# PA.net
KiCad netlist of a schematic drawn in EAGLE
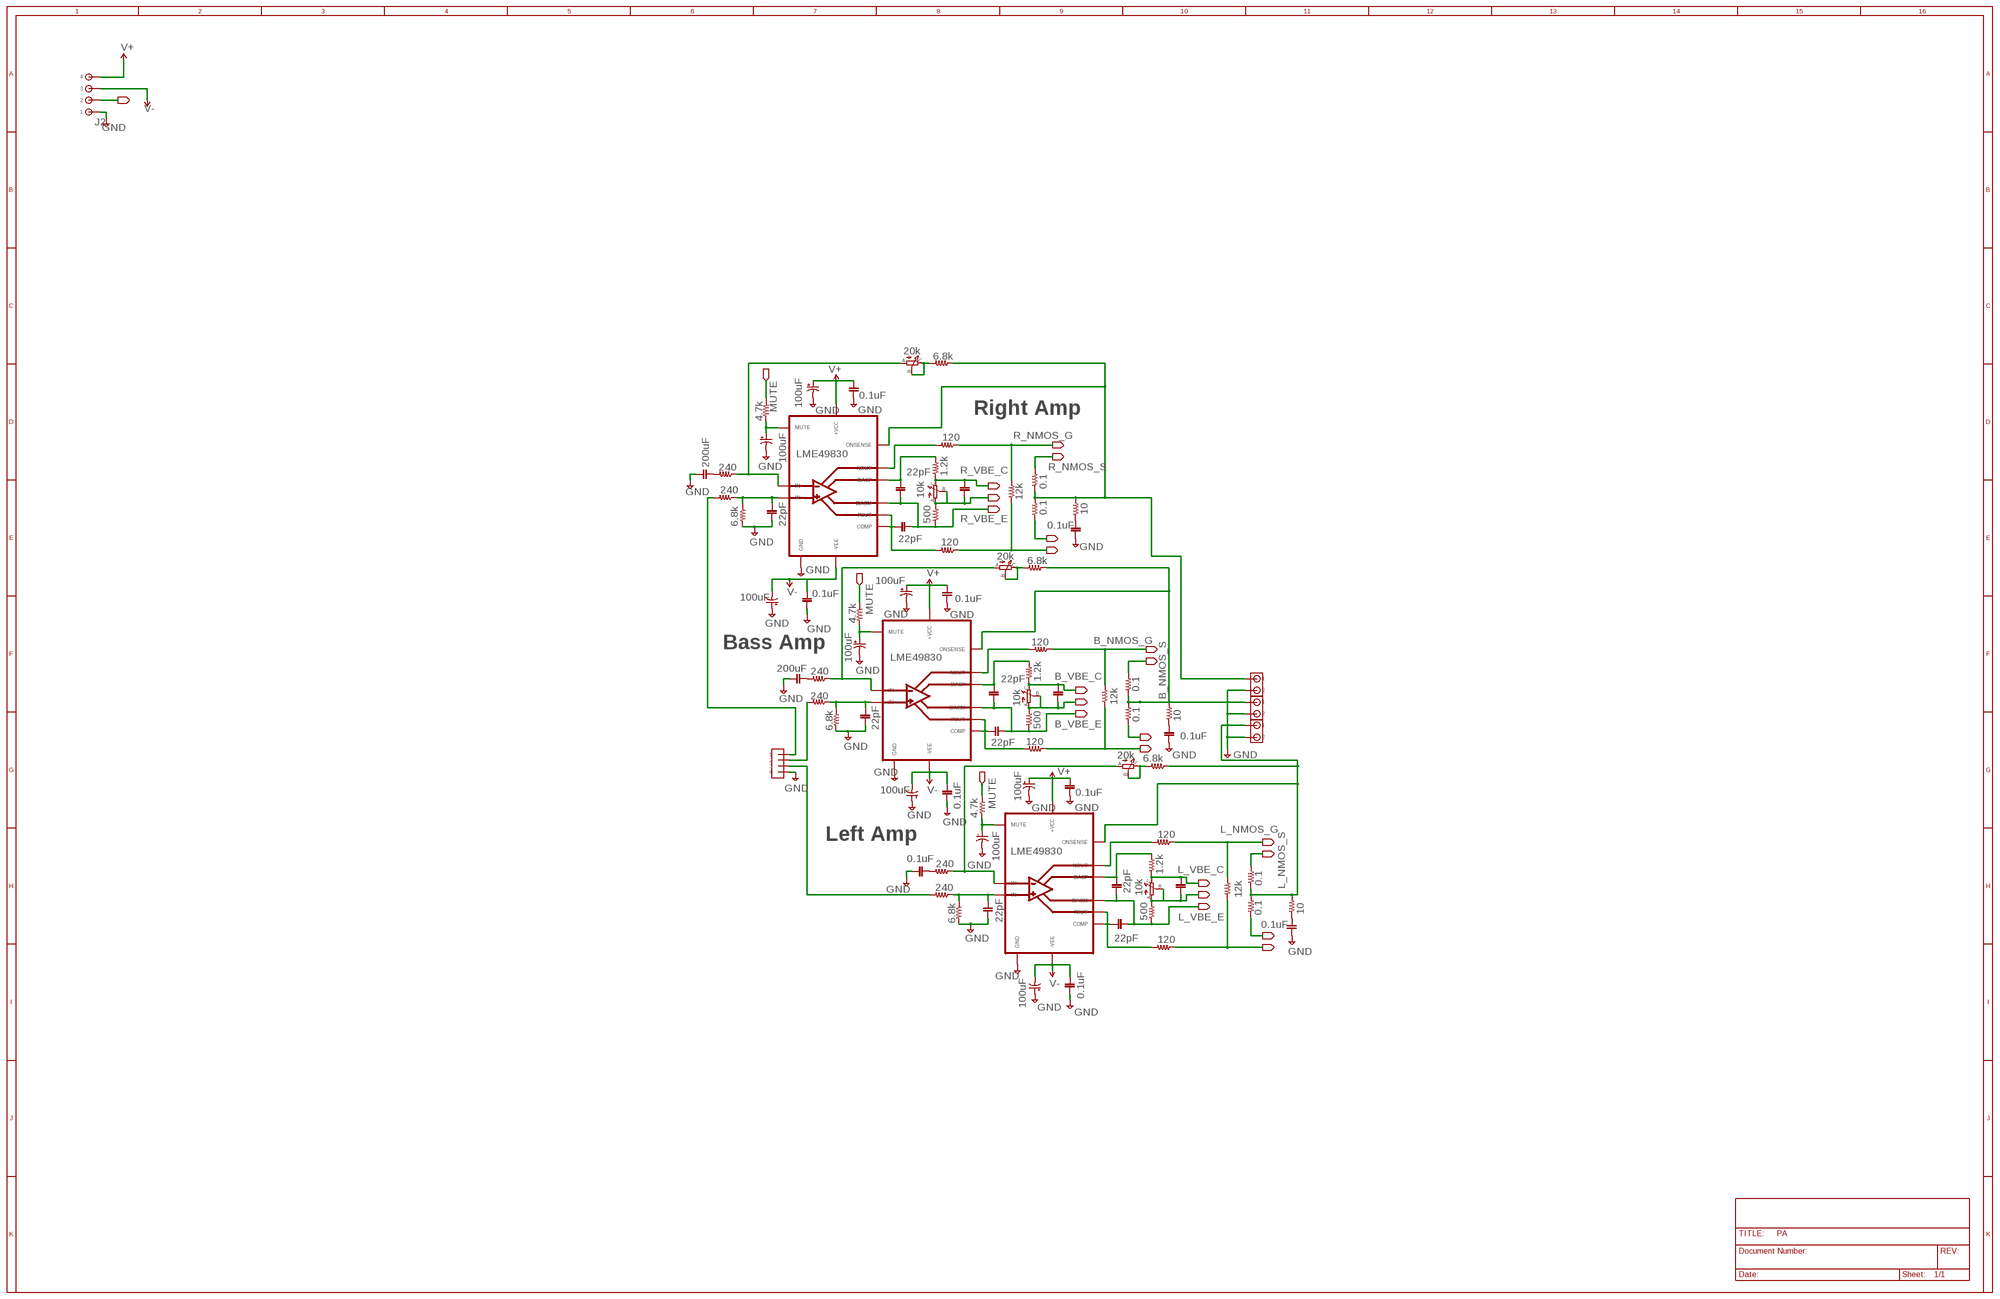
[diagram p0: schematic, sheet 1]

(export (version "E")
  (design (tool "Eeschema 10.0.6"))
  (components
    (comp (ref "C1")
      (value "22pF")
      (footprint "eagle-import:C050-024X044")
      (libsource (lib "eagle-import") (part "C-EU050-024X044"))
    )
    (comp (ref "C2")
      (value "100uF")
      (footprint "eagle-import:E2,5-6")
      (libsource (lib "eagle-import") (part "CPOL-USE2.5-6"))
    )
    (comp (ref "C3")
      (value "0.1uF")
      (footprint "eagle-import:C050-024X044")
      (libsource (lib "eagle-import") (part "C-EU050-024X044"))
    )
    (comp (ref "C4")
      (value "100uF")
      (footprint "eagle-import:E2,5-6")
      (libsource (lib "eagle-import") (part "CPOL-USE2.5-6"))
    )
    (comp (ref "C5")
      (value "0.1uF")
      (footprint "eagle-import:C050-024X044")
      (libsource (lib "eagle-import") (part "C-EU050-024X044"))
    )
    (comp (ref "C6")
      (value "100uF")
      (footprint "eagle-import:E2,5-6")
      (libsource (lib "eagle-import") (part "CPOL-USE2.5-6"))
    )
    (comp (ref "C7")
      (value "200uF")
      (footprint "eagle-import:C050-024X044")
      (libsource (lib "eagle-import") (part "C-EU050-024X044"))
    )
    (comp (ref "C8")
      (value "22pF")
      (footprint "eagle-import:C050-024X044")
      (libsource (lib "eagle-import") (part "C-EU050-024X044"))
    )
    (comp (ref "C9")
      (value "22pF")
      (footprint "eagle-import:C050-024X044")
      (libsource (lib "eagle-import") (part "C-EU050-024X044"))
    )
    (comp (ref "C10")
      (value "22pF")
      (footprint "eagle-import:C050-024X044")
      (libsource (lib "eagle-import") (part "C-EU050-024X044"))
    )
    (comp (ref "C15")
      (value "0.1uF")
      (footprint "eagle-import:C050-024X044")
      (libsource (lib "eagle-import") (part "C-EU050-024X044"))
    )
    (comp (ref "C16")
      (value "100uF")
      (footprint "eagle-import:E2,5-6")
      (libsource (lib "eagle-import") (part "CPOL-USE2.5-6"))
    )
    (comp (ref "C17")
      (value "100uF")
      (footprint "eagle-import:E2,5-6")
      (libsource (lib "eagle-import") (part "CPOL-USE2.5-6"))
    )
    (comp (ref "C18")
      (value "0.1uF")
      (footprint "eagle-import:C050-024X044")
      (libsource (lib "eagle-import") (part "C-EU050-024X044"))
    )
    (comp (ref "C19")
      (value "0.1uF")
      (footprint "eagle-import:C050-024X044")
      (libsource (lib "eagle-import") (part "C-EU050-024X044"))
    )
    (comp (ref "C20")
      (value "22pF")
      (footprint "eagle-import:C050-024X044")
      (libsource (lib "eagle-import") (part "C-EU050-024X044"))
    )
    (comp (ref "C21")
      (value "22pF")
      (footprint "eagle-import:C050-024X044")
      (libsource (lib "eagle-import") (part "C-EU050-024X044"))
    )
    (comp (ref "C22")
      (value "22pF")
      (footprint "eagle-import:C050-024X044")
      (libsource (lib "eagle-import") (part "C-EU050-024X044"))
    )
    (comp (ref "C27")
      (value "0.1uF")
      (footprint "eagle-import:C050-024X044")
      (libsource (lib "eagle-import") (part "C-EU050-024X044"))
    )
    (comp (ref "C28")
      (value "100uF")
      (footprint "eagle-import:E2,5-6")
      (libsource (lib "eagle-import") (part "CPOL-USE2.5-6"))
    )
    (comp (ref "C29")
      (value "22pF")
      (footprint "eagle-import:C050-024X044")
      (libsource (lib "eagle-import") (part "C-EU050-024X044"))
    )
    (comp (ref "C30")
      (value "200uF")
      (footprint "eagle-import:C050-024X044")
      (libsource (lib "eagle-import") (part "C-EU050-024X044"))
    )
    (comp (ref "C31")
      (value "100uF")
      (footprint "eagle-import:E2,5-6")
      (libsource (lib "eagle-import") (part "CPOL-USE2.5-6"))
    )
    (comp (ref "C32")
      (value "100uF")
      (footprint "eagle-import:E2,5-6")
      (libsource (lib "eagle-import") (part "CPOL-USE2.5-6"))
    )
    (comp (ref "C33")
      (value "0.1uF")
      (footprint "eagle-import:C050-024X044")
      (libsource (lib "eagle-import") (part "C-EU050-024X044"))
    )
    (comp (ref "C34")
      (value "0.1uF")
      (footprint "eagle-import:C050-024X044")
      (libsource (lib "eagle-import") (part "C-EU050-024X044"))
    )
    (comp (ref "C35")
      (value "22pF")
      (footprint "eagle-import:C050-024X044")
      (libsource (lib "eagle-import") (part "C-EU050-024X044"))
    )
    (comp (ref "C36")
      (value "22pF")
      (footprint "eagle-import:C050-024X044")
      (libsource (lib "eagle-import") (part "C-EU050-024X044"))
    )
    (comp (ref "C37")
      (value "22pF")
      (footprint "eagle-import:C050-024X044")
      (libsource (lib "eagle-import") (part "C-EU050-024X044"))
    )
    (comp (ref "C42")
      (value "0.1uF")
      (footprint "eagle-import:C050-024X044")
      (libsource (lib "eagle-import") (part "C-EU050-024X044"))
    )
    (comp (ref "C43")
      (value "100uF")
      (footprint "eagle-import:E2,5-6")
      (libsource (lib "eagle-import") (part "CPOL-USE2.5-6"))
    )
    (comp (ref "C44")
      (value "22pF")
      (footprint "eagle-import:C050-024X044")
      (libsource (lib "eagle-import") (part "C-EU050-024X044"))
    )
    (comp (ref "C45")
      (value "0.1uF")
      (footprint "eagle-import:C050-024X044")
      (libsource (lib "eagle-import") (part "C-EU050-024X044"))
    )
    (comp (ref "J1")
      (value "4_PIN_AMPCONN")
      (footprint "eagle-import:4_PIN_AMPCON")
      (libsource (lib "eagle-import") (part "4_PIN_AMPCONN"))
    )
    (comp (ref "J2")
      (value "1984633")
      (footprint "eagle-import:1984633")
      (libsource (lib "eagle-import") (part "1984633"))
    )
    (comp (ref "J3")
      (value "2TERMINAL_SPEAKER")
      (footprint "eagle-import:2TERMINAL_SPEAKER")
      (libsource (lib "eagle-import") (part "2TERMINAL_SPEAKER"))
    )
    (comp (ref "J4")
      (value "2TERMINAL_SPEAKER")
      (footprint "eagle-import:2TERMINAL_SPEAKER")
      (libsource (lib "eagle-import") (part "2TERMINAL_SPEAKER"))
    )
    (comp (ref "J5")
      (value "2TERMINAL_SPEAKER")
      (footprint "eagle-import:2TERMINAL_SPEAKER")
      (libsource (lib "eagle-import") (part "2TERMINAL_SPEAKER"))
    )
    (comp (ref "PR1")
      (value "0.1")
      (footprint "eagle-import:0617V")
      (libsource (lib "eagle-import") (part "R-US_0617/5V"))
    )
    (comp (ref "PR2")
      (value "0.1")
      (footprint "eagle-import:0617V")
      (libsource (lib "eagle-import") (part "R-US_0617/5V"))
    )
    (comp (ref "PR3")
      (value "0.1")
      (footprint "eagle-import:0617V")
      (libsource (lib "eagle-import") (part "R-US_0617/5V"))
    )
    (comp (ref "PR4")
      (value "0.1")
      (footprint "eagle-import:0617V")
      (libsource (lib "eagle-import") (part "R-US_0617/5V"))
    )
    (comp (ref "PR5")
      (value "0.1")
      (footprint "eagle-import:0617V")
      (libsource (lib "eagle-import") (part "R-US_0617/5V"))
    )
    (comp (ref "PR6")
      (value "0.1")
      (footprint "eagle-import:0617V")
      (libsource (lib "eagle-import") (part "R-US_0617/5V"))
    )
    (comp (ref "R1")
      (value "240")
      (footprint "eagle-import:0204V")
      (libsource (lib "eagle-import") (part "R-US_0204/2V"))
    )
    (comp (ref "R2")
      (value "6.8k")
      (footprint "eagle-import:0204V")
      (libsource (lib "eagle-import") (part "R-US_0204/2V"))
    )
    (comp (ref "R3")
      (value "1.2k")
      (footprint "eagle-import:0204V")
      (libsource (lib "eagle-import") (part "R-US_0204/2V"))
    )
    (comp (ref "R4")
      (value "500")
      (footprint "eagle-import:0204V")
      (libsource (lib "eagle-import") (part "R-US_0204/2V"))
    )
    (comp (ref "R5")
      (value "12k")
      (footprint "eagle-import:0204V")
      (libsource (lib "eagle-import") (part "R-US_0204/2V"))
    )
    (comp (ref "R6")
      (value "120")
      (footprint "eagle-import:0204V")
      (libsource (lib "eagle-import") (part "R-US_0204/2V"))
    )
    (comp (ref "R7")
      (value "120")
      (footprint "eagle-import:0204V")
      (libsource (lib "eagle-import") (part "R-US_0204/2V"))
    )
    (comp (ref "R8")
      (value "10")
      (footprint "eagle-import:0309V")
      (libsource (lib "eagle-import") (part "R-US_0309/V"))
    )
    (comp (ref "R9")
      (value "4.7k")
      (footprint "eagle-import:0204V")
      (libsource (lib "eagle-import") (part "R-US_0204/2V"))
    )
    (comp (ref "R10")
      (value "6.8k")
      (footprint "eagle-import:0204V")
      (libsource (lib "eagle-import") (part "R-US_0204/2V"))
    )
    (comp (ref "R11")
      (value "240")
      (footprint "eagle-import:0204V")
      (libsource (lib "eagle-import") (part "R-US_0204/2V"))
    )
    (comp (ref "R12")
      (value "240")
      (footprint "eagle-import:0204V")
      (libsource (lib "eagle-import") (part "R-US_0204/2V"))
    )
    (comp (ref "R13")
      (value "6.8k")
      (footprint "eagle-import:0204V")
      (libsource (lib "eagle-import") (part "R-US_0204/2V"))
    )
    (comp (ref "R14")
      (value "1.2k")
      (footprint "eagle-import:0204V")
      (libsource (lib "eagle-import") (part "R-US_0204/2V"))
    )
    (comp (ref "R15")
      (value "500")
      (footprint "eagle-import:0204V")
      (libsource (lib "eagle-import") (part "R-US_0204/2V"))
    )
    (comp (ref "R16")
      (value "12k")
      (footprint "eagle-import:0204V")
      (libsource (lib "eagle-import") (part "R-US_0204/2V"))
    )
    (comp (ref "R17")
      (value "120")
      (footprint "eagle-import:0204V")
      (libsource (lib "eagle-import") (part "R-US_0204/2V"))
    )
    (comp (ref "R18")
      (value "120")
      (footprint "eagle-import:0204V")
      (libsource (lib "eagle-import") (part "R-US_0204/2V"))
    )
    (comp (ref "R19")
      (value "10")
      (footprint "eagle-import:0309V")
      (libsource (lib "eagle-import") (part "R-US_0309/V"))
    )
    (comp (ref "R20")
      (value "4.7k")
      (footprint "eagle-import:0204V")
      (libsource (lib "eagle-import") (part "R-US_0204/2V"))
    )
    (comp (ref "R21")
      (value "6.8k")
      (footprint "eagle-import:0204V")
      (libsource (lib "eagle-import") (part "R-US_0204/2V"))
    )
    (comp (ref "R22")
      (value "240")
      (footprint "eagle-import:0204V")
      (libsource (lib "eagle-import") (part "R-US_0204/2V"))
    )
    (comp (ref "R23")
      (value "240")
      (footprint "eagle-import:0204V")
      (libsource (lib "eagle-import") (part "R-US_0204/2V"))
    )
    (comp (ref "R24")
      (value "6.8k")
      (footprint "eagle-import:0204V")
      (libsource (lib "eagle-import") (part "R-US_0204/2V"))
    )
    (comp (ref "R44")
      (value "1.2k")
      (footprint "eagle-import:0204V")
      (libsource (lib "eagle-import") (part "R-US_0204/2V"))
    )
    (comp (ref "R45")
      (value "500")
      (footprint "eagle-import:0204V")
      (libsource (lib "eagle-import") (part "R-US_0204/2V"))
    )
    (comp (ref "R46")
      (value "12k")
      (footprint "eagle-import:0204V")
      (libsource (lib "eagle-import") (part "R-US_0204/2V"))
    )
    (comp (ref "R47")
      (value "120")
      (footprint "eagle-import:0204V")
      (libsource (lib "eagle-import") (part "R-US_0204/2V"))
    )
    (comp (ref "R48")
      (value "120")
      (footprint "eagle-import:0204V")
      (libsource (lib "eagle-import") (part "R-US_0204/2V"))
    )
    (comp (ref "R51")
      (value "10")
      (footprint "eagle-import:0309V")
      (libsource (lib "eagle-import") (part "R-US_0309/V"))
    )
    (comp (ref "R52")
      (value "4.7k")
      (footprint "eagle-import:0204V")
      (libsource (lib "eagle-import") (part "R-US_0204/2V"))
    )
    (comp (ref "R55")
      (value "240")
      (footprint "eagle-import:0204V")
      (libsource (lib "eagle-import") (part "R-US_0204/2V"))
    )
    (comp (ref "R56")
      (value "6.8k")
      (footprint "eagle-import:0204V")
      (libsource (lib "eagle-import") (part "R-US_0204/2V"))
    )
    (comp (ref "U1")
      (value "LME49830")
      (footprint "eagle-import:NDN0015A")
      (libsource (lib "eagle-import") (part "LME49830"))
    )
    (comp (ref "U2")
      (value "LME49830")
      (footprint "eagle-import:NDN0015A")
      (libsource (lib "eagle-import") (part "LME49830"))
    )
    (comp (ref "U3")
      (value "LME49830")
      (footprint "eagle-import:NDN0015A")
      (libsource (lib "eagle-import") (part "LME49830"))
    )
    (comp (ref "VR1")
      (value "20k")
      (footprint "eagle-import:EVM2W")
      (libsource (lib "eagle-import") (part "EVM2W"))
    )
    (comp (ref "VR2")
      (value "10k")
      (footprint "eagle-import:EVM2W")
      (libsource (lib "eagle-import") (part "EVM2W"))
    )
    (comp (ref "VR3")
      (value "20k")
      (footprint "eagle-import:EVM2W")
      (libsource (lib "eagle-import") (part "EVM2W"))
    )
    (comp (ref "VR4")
      (value "10k")
      (footprint "eagle-import:EVM2W")
      (libsource (lib "eagle-import") (part "EVM2W"))
    )
    (comp (ref "VR5")
      (value "20k")
      (footprint "eagle-import:EVM2W")
      (libsource (lib "eagle-import") (part "EVM2W"))
    )
    (comp (ref "VR6")
      (value "10k")
      (footprint "eagle-import:EVM2W")
      (libsource (lib "eagle-import") (part "EVM2W"))
    )
  )
  (nets
    (net (code "1") (name "/B_NMOS_G") (class "Default")
      (node (ref "R5") (pin "2") (pinfunction "2_2") (pintype "passive"))
      (node (ref "R7") (pin "1") (pinfunction "1_1") (pintype "passive"))
    )
    (net (code "2") (name "/B_NMOS_S") (class "Default")
      (node (ref "PR2") (pin "2") (pinfunction "2_2") (pintype "passive"))
    )
    (net (code "3") (name "/B_VBE_C") (class "Default")
      (node (ref "C21") (pin "2") (pinfunction "2_2") (pintype "passive"))
      (node (ref "R3") (pin "1") (pinfunction "1_1") (pintype "passive"))
      (node (ref "VR4") (pin "C") (pinfunction "C_C") (pintype "passive"))
    )
    (net (code "4") (name "/B_VBE_E") (class "Default")
      (node (ref "C20") (pin "1") (pinfunction "1_1") (pintype "passive"))
      (node (ref "C22") (pin "1") (pinfunction "1_1") (pintype "passive"))
      (node (ref "R4") (pin "1") (pinfunction "1_1") (pintype "passive"))
      (node (ref "U2") (pin "P11") (pinfunction "BIASM_P11") (pintype "bidirectional"))
    )
    (net (code "5") (name "/L_NMOS_G") (class "Default")
      (node (ref "R16") (pin "2") (pinfunction "2_2") (pintype "passive"))
      (node (ref "R18") (pin "1") (pinfunction "1_1") (pintype "passive"))
    )
    (net (code "6") (name "/L_NMOS_S") (class "Default")
      (node (ref "PR4") (pin "2") (pinfunction "2_2") (pintype "passive"))
    )
    (net (code "7") (name "/L_VBE_C") (class "Default")
      (node (ref "C36") (pin "2") (pinfunction "2_2") (pintype "passive"))
      (node (ref "R14") (pin "1") (pinfunction "1_1") (pintype "passive"))
      (node (ref "VR6") (pin "C") (pinfunction "C_C") (pintype "passive"))
    )
    (net (code "8") (name "/L_VBE_E") (class "Default")
      (node (ref "C35") (pin "1") (pinfunction "1_1") (pintype "passive"))
      (node (ref "C37") (pin "1") (pinfunction "1_1") (pintype "passive"))
      (node (ref "R15") (pin "1") (pinfunction "1_1") (pintype "passive"))
      (node (ref "U3") (pin "P11") (pinfunction "BIASM_P11") (pintype "bidirectional"))
    )
    (net (code "9") (name "/MUTE") (class "Default")
      (node (ref "J2") (pin "P$2") (pinfunction "2_P$2") (pintype "passive"))
      (node (ref "R20") (pin "1") (pinfunction "1_1") (pintype "passive"))
      (node (ref "R52") (pin "1") (pinfunction "1_1") (pintype "passive"))
      (node (ref "R9") (pin "1") (pinfunction "1_1") (pintype "passive"))
    )
    (net (code "10") (name "/R_NMOS_G") (class "Default")
      (node (ref "R46") (pin "2") (pinfunction "2_2") (pintype "passive"))
      (node (ref "R48") (pin "1") (pinfunction "1_1") (pintype "passive"))
    )
    (net (code "11") (name "/R_NMOS_S") (class "Default")
      (node (ref "PR6") (pin "2") (pinfunction "2_2") (pintype "passive"))
    )
    (net (code "12") (name "/R_VBE_C") (class "Default")
      (node (ref "C10") (pin "2") (pinfunction "2_2") (pintype "passive"))
      (node (ref "R44") (pin "1") (pinfunction "1_1") (pintype "passive"))
      (node (ref "VR2") (pin "C") (pinfunction "C_C") (pintype "passive"))
    )
    (net (code "13") (name "/R_VBE_E") (class "Default")
      (node (ref "C8") (pin "1") (pinfunction "1_1") (pintype "passive"))
      (node (ref "C9") (pin "1") (pinfunction "1_1") (pintype "passive"))
      (node (ref "R45") (pin "1") (pinfunction "1_1") (pintype "passive"))
      (node (ref "U1") (pin "P11") (pinfunction "BIASM_P11") (pintype "bidirectional"))
    )
    (net (code "14") (name "GND") (class "Default")
      (node (ref "C1") (pin "1") (pinfunction "1_1") (pintype "passive"))
      (node (ref "C15") (pin "1") (pinfunction "1_1") (pintype "passive"))
      (node (ref "C16") (pin "+") (pinfunction "+_+") (pintype "passive"))
      (node (ref "C17") (pin "-") (pinfunction "-_-") (pintype "passive"))
      (node (ref "C18") (pin "1") (pinfunction "1_1") (pintype "passive"))
      (node (ref "C19") (pin "2") (pinfunction "2_2") (pintype "passive"))
      (node (ref "C2") (pin "+") (pinfunction "+_+") (pintype "passive"))
      (node (ref "C27") (pin "1") (pinfunction "1_1") (pintype "passive"))
      (node (ref "C28") (pin "-") (pinfunction "-_-") (pintype "passive"))
      (node (ref "C29") (pin "1") (pinfunction "1_1") (pintype "passive"))
      (node (ref "C3") (pin "1") (pinfunction "1_1") (pintype "passive"))
      (node (ref "C30") (pin "1") (pinfunction "1_1") (pintype "passive"))
      (node (ref "C31") (pin "+") (pinfunction "+_+") (pintype "passive"))
      (node (ref "C32") (pin "-") (pinfunction "-_-") (pintype "passive"))
      (node (ref "C33") (pin "1") (pinfunction "1_1") (pintype "passive"))
      (node (ref "C34") (pin "2") (pinfunction "2_2") (pintype "passive"))
      (node (ref "C4") (pin "-") (pinfunction "-_-") (pintype "passive"))
      (node (ref "C42") (pin "1") (pinfunction "1_1") (pintype "passive"))
      (node (ref "C43") (pin "-") (pinfunction "-_-") (pintype "passive"))
      (node (ref "C44") (pin "1") (pinfunction "1_1") (pintype "passive"))
      (node (ref "C45") (pin "1") (pinfunction "1_1") (pintype "passive"))
      (node (ref "C5") (pin "2") (pinfunction "2_2") (pintype "passive"))
      (node (ref "C6") (pin "-") (pinfunction "-_-") (pintype "passive"))
      (node (ref "C7") (pin "1") (pinfunction "1_1") (pintype "passive"))
      (node (ref "J1") (pin "4") (pinfunction "4_4") (pintype "passive"))
      (node (ref "J2") (pin "P$1") (pinfunction "1_P$1") (pintype "passive"))
      (node (ref "J3") (pin "P$2") (pinfunction "2_P$2") (pintype "passive"))
      (node (ref "J4") (pin "P$2") (pinfunction "2_P$2") (pintype "passive"))
      (node (ref "J5") (pin "P$2") (pinfunction "2_P$2") (pintype "passive"))
      (node (ref "R10") (pin "2") (pinfunction "2_2") (pintype "passive"))
      (node (ref "R2") (pin "2") (pinfunction "2_2") (pintype "passive"))
      (node (ref "R21") (pin "2") (pinfunction "2_2") (pintype "passive"))
      (node (ref "U1") (pin "P3") (pinfunction "GND_P3") (pintype "bidirectional"))
      (node (ref "U2") (pin "P3") (pinfunction "GND_P3") (pintype "bidirectional"))
      (node (ref "U3") (pin "P3") (pinfunction "GND_P3") (pintype "bidirectional"))
    )
    (net (code "15") (name "Net-(C7-Pad2)") (class "Default")
      (node (ref "C7") (pin "2") (pinfunction "2_2") (pintype "passive"))
      (node (ref "R55") (pin "2") (pinfunction "2_2") (pintype "passive"))
    )
    (net (code "16") (name "Net-(C10-Pad1)") (class "Default")
      (node (ref "C10") (pin "1") (pinfunction "1_1") (pintype "passive"))
      (node (ref "R45") (pin "2") (pinfunction "2_2") (pintype "passive"))
      (node (ref "VR2") (pin "A") (pinfunction "A_A") (pintype "passive"))
      (node (ref "VR2") (pin "B") (pinfunction "B_B") (pintype "passive"))
    )
    (net (code "17") (name "Net-(C15-Pad2)") (class "Default")
      (node (ref "C15") (pin "2") (pinfunction "2_2") (pintype "passive"))
      (node (ref "R51") (pin "1") (pinfunction "1_1") (pintype "passive"))
    )
    (net (code "18") (name "Net-(C21-Pad1)") (class "Default")
      (node (ref "C21") (pin "1") (pinfunction "1_1") (pintype "passive"))
      (node (ref "R4") (pin "2") (pinfunction "2_2") (pintype "passive"))
      (node (ref "VR4") (pin "A") (pinfunction "A_A") (pintype "passive"))
      (node (ref "VR4") (pin "B") (pinfunction "B_B") (pintype "passive"))
    )
    (net (code "19") (name "Net-(C27-Pad2)") (class "Default")
      (node (ref "C27") (pin "2") (pinfunction "2_2") (pintype "passive"))
      (node (ref "R8") (pin "1") (pinfunction "1_1") (pintype "passive"))
    )
    (net (code "20") (name "Net-(C30-Pad2)") (class "Default")
      (node (ref "C30") (pin "2") (pinfunction "2_2") (pintype "passive"))
      (node (ref "R12") (pin "2") (pinfunction "2_2") (pintype "passive"))
    )
    (net (code "21") (name "Net-(C36-Pad1)") (class "Default")
      (node (ref "C36") (pin "1") (pinfunction "1_1") (pintype "passive"))
      (node (ref "R15") (pin "2") (pinfunction "2_2") (pintype "passive"))
      (node (ref "VR6") (pin "A") (pinfunction "A_A") (pintype "passive"))
      (node (ref "VR6") (pin "B") (pinfunction "B_B") (pintype "passive"))
    )
    (net (code "22") (name "Net-(C42-Pad2)") (class "Default")
      (node (ref "C42") (pin "2") (pinfunction "2_2") (pintype "passive"))
      (node (ref "R19") (pin "1") (pinfunction "1_1") (pintype "passive"))
    )
    (net (code "23") (name "Net-(C45-Pad2)") (class "Default")
      (node (ref "C45") (pin "2") (pinfunction "2_2") (pintype "passive"))
      (node (ref "R23") (pin "2") (pinfunction "2_2") (pintype "passive"))
    )
    (net (code "24") (name "Net-(J1-Pad1)") (class "Default")
      (node (ref "J1") (pin "1") (pinfunction "1_1") (pintype "passive"))
      (node (ref "R1") (pin "2") (pinfunction "2_2") (pintype "passive"))
    )
    (net (code "25") (name "Net-(J1-Pad2)") (class "Default")
      (node (ref "J1") (pin "2") (pinfunction "2_2") (pintype "passive"))
      (node (ref "R11") (pin "2") (pinfunction "2_2") (pintype "passive"))
    )
    (net (code "26") (name "Net-(J1-Pad3)") (class "Default")
      (node (ref "J1") (pin "3") (pinfunction "3_3") (pintype "passive"))
      (node (ref "R22") (pin "2") (pinfunction "2_2") (pintype "passive"))
    )
    (net (code "27") (name "Net-(J3-1)") (class "Default")
      (node (ref "J3") (pin "P$1") (pinfunction "1_P$1") (pintype "passive"))
      (node (ref "PR5") (pin "2") (pinfunction "2_2") (pintype "passive"))
      (node (ref "PR6") (pin "1") (pinfunction "1_1") (pintype "passive"))
      (node (ref "R51") (pin "2") (pinfunction "2_2") (pintype "passive"))
      (node (ref "R56") (pin "1") (pinfunction "1_1") (pintype "passive"))
      (node (ref "U1") (pin "P$8") (pinfunction "ONSENSE_P$8") (pintype "bidirectional"))
    )
    (net (code "28") (name "Net-(J4-1)") (class "Default")
      (node (ref "J4") (pin "P$1") (pinfunction "1_P$1") (pintype "passive"))
      (node (ref "PR1") (pin "2") (pinfunction "2_2") (pintype "passive"))
      (node (ref "PR2") (pin "1") (pinfunction "1_1") (pintype "passive"))
      (node (ref "R13") (pin "1") (pinfunction "1_1") (pintype "passive"))
      (node (ref "R8") (pin "2") (pinfunction "2_2") (pintype "passive"))
      (node (ref "U2") (pin "P$8") (pinfunction "ONSENSE_P$8") (pintype "bidirectional"))
    )
    (net (code "29") (name "Net-(J5-1)") (class "Default")
      (node (ref "J5") (pin "P$1") (pinfunction "1_P$1") (pintype "passive"))
      (node (ref "PR3") (pin "2") (pinfunction "2_2") (pintype "passive"))
      (node (ref "PR4") (pin "1") (pinfunction "1_1") (pintype "passive"))
      (node (ref "R19") (pin "2") (pinfunction "2_2") (pintype "passive"))
      (node (ref "R24") (pin "1") (pinfunction "1_1") (pintype "passive"))
      (node (ref "U3") (pin "P$8") (pinfunction "ONSENSE_P$8") (pintype "bidirectional"))
    )
    (net (code "30") (name "Net-(R5-Pad1)") (class "Default")
      (node (ref "R5") (pin "1") (pinfunction "1_1") (pintype "passive"))
      (node (ref "R6") (pin "1") (pinfunction "1_1") (pintype "passive"))
    )
    (net (code "31") (name "Net-(R13-Pad2)") (class "Default")
      (node (ref "R13") (pin "2") (pinfunction "2_2") (pintype "passive"))
      (node (ref "VR3") (pin "B") (pinfunction "B_B") (pintype "passive"))
      (node (ref "VR3") (pin "C") (pinfunction "C_C") (pintype "passive"))
    )
    (net (code "32") (name "Net-(R16-Pad1)") (class "Default")
      (node (ref "R16") (pin "1") (pinfunction "1_1") (pintype "passive"))
      (node (ref "R17") (pin "1") (pinfunction "1_1") (pintype "passive"))
    )
    (net (code "33") (name "Net-(R24-Pad2)") (class "Default")
      (node (ref "R24") (pin "2") (pinfunction "2_2") (pintype "passive"))
      (node (ref "VR5") (pin "B") (pinfunction "B_B") (pintype "passive"))
      (node (ref "VR5") (pin "C") (pinfunction "C_C") (pintype "passive"))
    )
    (net (code "34") (name "Net-(R46-Pad1)") (class "Default")
      (node (ref "R46") (pin "1") (pinfunction "1_1") (pintype "passive"))
      (node (ref "R47") (pin "1") (pinfunction "1_1") (pintype "passive"))
    )
    (net (code "35") (name "Net-(R56-Pad2)") (class "Default")
      (node (ref "R56") (pin "2") (pinfunction "2_2") (pintype "passive"))
      (node (ref "VR1") (pin "B") (pinfunction "B_B") (pintype "passive"))
      (node (ref "VR1") (pin "C") (pinfunction "C_C") (pintype "passive"))
    )
    (net (code "36") (name "Net-(U1-BIASP)") (class "Default")
      (node (ref "C9") (pin "2") (pinfunction "2_2") (pintype "passive"))
      (node (ref "R44") (pin "2") (pinfunction "2_2") (pintype "passive"))
      (node (ref "U1") (pin "P12") (pinfunction "BIASP_P12") (pintype "bidirectional"))
    )
    (net (code "37") (name "Net-(U1-COMP)") (class "Default")
      (node (ref "C8") (pin "2") (pinfunction "2_2") (pintype "passive"))
      (node (ref "U1") (pin "P6") (pinfunction "COMP_P6") (pintype "bidirectional"))
    )
    (net (code "38") (name "Net-(U1-IN+)") (class "Default")
      (node (ref "C1") (pin "2") (pinfunction "2_2") (pintype "passive"))
      (node (ref "R1") (pin "1") (pinfunction "1_1") (pintype "passive"))
      (node (ref "R2") (pin "1") (pinfunction "1_1") (pintype "passive"))
      (node (ref "U1") (pin "P4") (pinfunction "IN+_P4") (pintype "bidirectional"))
    )
    (net (code "39") (name "Net-(U1-IN-)") (class "Default")
      (node (ref "R55") (pin "1") (pinfunction "1_1") (pintype "passive"))
      (node (ref "U1") (pin "P5") (pinfunction "IN-_P5") (pintype "bidirectional"))
      (node (ref "VR1") (pin "A") (pinfunction "A_A") (pintype "passive"))
    )
    (net (code "40") (name "Net-(U1-MUTE)") (class "Default")
      (node (ref "C6") (pin "+") (pinfunction "+_+") (pintype "passive"))
      (node (ref "R52") (pin "2") (pinfunction "2_2") (pintype "passive"))
      (node (ref "U1") (pin "P2") (pinfunction "MUTE_P2") (pintype "bidirectional"))
    )
    (net (code "41") (name "Net-(U1-NOUT)") (class "Default")
      (node (ref "R48") (pin "2") (pinfunction "2_2") (pintype "passive"))
      (node (ref "U1") (pin "P14") (pinfunction "NOUT_P14") (pintype "bidirectional"))
    )
    (net (code "42") (name "Net-(U1-POUT)") (class "Default")
      (node (ref "R47") (pin "2") (pinfunction "2_2") (pintype "passive"))
      (node (ref "U1") (pin "P13") (pinfunction "POUT_P13") (pintype "bidirectional"))
    )
    (net (code "43") (name "Net-(U2-BIASP)") (class "Default")
      (node (ref "C20") (pin "2") (pinfunction "2_2") (pintype "passive"))
      (node (ref "R3") (pin "2") (pinfunction "2_2") (pintype "passive"))
      (node (ref "U2") (pin "P12") (pinfunction "BIASP_P12") (pintype "bidirectional"))
    )
    (net (code "44") (name "Net-(U2-COMP)") (class "Default")
      (node (ref "C22") (pin "2") (pinfunction "2_2") (pintype "passive"))
      (node (ref "U2") (pin "P6") (pinfunction "COMP_P6") (pintype "bidirectional"))
    )
    (net (code "45") (name "Net-(U2-IN+)") (class "Default")
      (node (ref "C29") (pin "2") (pinfunction "2_2") (pintype "passive"))
      (node (ref "R10") (pin "1") (pinfunction "1_1") (pintype "passive"))
      (node (ref "R11") (pin "1") (pinfunction "1_1") (pintype "passive"))
      (node (ref "U2") (pin "P4") (pinfunction "IN+_P4") (pintype "bidirectional"))
    )
    (net (code "46") (name "Net-(U2-IN-)") (class "Default")
      (node (ref "R12") (pin "1") (pinfunction "1_1") (pintype "passive"))
      (node (ref "U2") (pin "P5") (pinfunction "IN-_P5") (pintype "bidirectional"))
      (node (ref "VR3") (pin "A") (pinfunction "A_A") (pintype "passive"))
    )
    (net (code "47") (name "Net-(U2-MUTE)") (class "Default")
      (node (ref "C28") (pin "+") (pinfunction "+_+") (pintype "passive"))
      (node (ref "R9") (pin "2") (pinfunction "2_2") (pintype "passive"))
      (node (ref "U2") (pin "P2") (pinfunction "MUTE_P2") (pintype "bidirectional"))
    )
    (net (code "48") (name "Net-(U2-NOUT)") (class "Default")
      (node (ref "R7") (pin "2") (pinfunction "2_2") (pintype "passive"))
      (node (ref "U2") (pin "P14") (pinfunction "NOUT_P14") (pintype "bidirectional"))
    )
    (net (code "49") (name "Net-(U2-POUT)") (class "Default")
      (node (ref "R6") (pin "2") (pinfunction "2_2") (pintype "passive"))
      (node (ref "U2") (pin "P13") (pinfunction "POUT_P13") (pintype "bidirectional"))
    )
    (net (code "50") (name "Net-(U3-BIASP)") (class "Default")
      (node (ref "C35") (pin "2") (pinfunction "2_2") (pintype "passive"))
      (node (ref "R14") (pin "2") (pinfunction "2_2") (pintype "passive"))
      (node (ref "U3") (pin "P12") (pinfunction "BIASP_P12") (pintype "bidirectional"))
    )
    (net (code "51") (name "Net-(U3-COMP)") (class "Default")
      (node (ref "C37") (pin "2") (pinfunction "2_2") (pintype "passive"))
      (node (ref "U3") (pin "P6") (pinfunction "COMP_P6") (pintype "bidirectional"))
    )
    (net (code "52") (name "Net-(U3-IN+)") (class "Default")
      (node (ref "C44") (pin "2") (pinfunction "2_2") (pintype "passive"))
      (node (ref "R21") (pin "1") (pinfunction "1_1") (pintype "passive"))
      (node (ref "R22") (pin "1") (pinfunction "1_1") (pintype "passive"))
      (node (ref "U3") (pin "P4") (pinfunction "IN+_P4") (pintype "bidirectional"))
    )
    (net (code "53") (name "Net-(U3-IN-)") (class "Default")
      (node (ref "R23") (pin "1") (pinfunction "1_1") (pintype "passive"))
      (node (ref "U3") (pin "P5") (pinfunction "IN-_P5") (pintype "bidirectional"))
      (node (ref "VR5") (pin "A") (pinfunction "A_A") (pintype "passive"))
    )
    (net (code "54") (name "Net-(U3-MUTE)") (class "Default")
      (node (ref "C43") (pin "+") (pinfunction "+_+") (pintype "passive"))
      (node (ref "R20") (pin "2") (pinfunction "2_2") (pintype "passive"))
      (node (ref "U3") (pin "P2") (pinfunction "MUTE_P2") (pintype "bidirectional"))
    )
    (net (code "55") (name "Net-(U3-NOUT)") (class "Default")
      (node (ref "R18") (pin "2") (pinfunction "2_2") (pintype "passive"))
      (node (ref "U3") (pin "P14") (pinfunction "NOUT_P14") (pintype "bidirectional"))
    )
    (net (code "56") (name "Net-(U3-POUT)") (class "Default")
      (node (ref "R17") (pin "2") (pinfunction "2_2") (pintype "passive"))
      (node (ref "U3") (pin "P13") (pinfunction "POUT_P13") (pintype "bidirectional"))
    )
    (net (code "57") (name "V+") (class "Default")
      (node (ref "C17") (pin "+") (pinfunction "+_+") (pintype "passive"))
      (node (ref "C19") (pin "1") (pinfunction "1_1") (pintype "passive"))
      (node (ref "C32") (pin "+") (pinfunction "+_+") (pintype "passive"))
      (node (ref "C34") (pin "1") (pinfunction "1_1") (pintype "passive"))
      (node (ref "C4") (pin "+") (pinfunction "+_+") (pintype "passive"))
      (node (ref "C5") (pin "1") (pinfunction "1_1") (pintype "passive"))
      (node (ref "J2") (pin "P$4") (pinfunction "4_P$4") (pintype "passive"))
      (node (ref "U1") (pin "P15") (pinfunction "+VCC_P15") (pintype "passive"))
      (node (ref "U2") (pin "P15") (pinfunction "+VCC_P15") (pintype "passive"))
      (node (ref "U3") (pin "P15") (pinfunction "+VCC_P15") (pintype "passive"))
    )
    (net (code "58") (name "V-") (class "Default")
      (node (ref "C16") (pin "-") (pinfunction "-_-") (pintype "passive"))
      (node (ref "C18") (pin "2") (pinfunction "2_2") (pintype "passive"))
      (node (ref "C2") (pin "-") (pinfunction "-_-") (pintype "passive"))
      (node (ref "C3") (pin "2") (pinfunction "2_2") (pintype "passive"))
      (node (ref "C31") (pin "-") (pinfunction "-_-") (pintype "passive"))
      (node (ref "C33") (pin "2") (pinfunction "2_2") (pintype "passive"))
      (node (ref "J2") (pin "P$3") (pinfunction "3_P$3") (pintype "passive"))
      (node (ref "U1") (pin "P10") (pinfunction "-VEE_P10") (pintype "power_in"))
      (node (ref "U2") (pin "P10") (pinfunction "-VEE_P10") (pintype "power_in"))
      (node (ref "U3") (pin "P10") (pinfunction "-VEE_P10") (pintype "power_in"))
    )
    (net (code "59") (name "unconnected-(PR1-Pad1)") (class "Default")
      (node (ref "PR1") (pin "1") (pinfunction "1_1") (pintype "passive"))
    )
    (net (code "60") (name "unconnected-(PR3-Pad1)") (class "Default")
      (node (ref "PR3") (pin "1") (pinfunction "1_1") (pintype "passive"))
    )
    (net (code "61") (name "unconnected-(PR5-Pad1)") (class "Default")
      (node (ref "PR5") (pin "1") (pinfunction "1_1") (pintype "passive"))
    )
  )
)
